# Boat.net
KiCad netlist of a schematic drawn in EAGLE
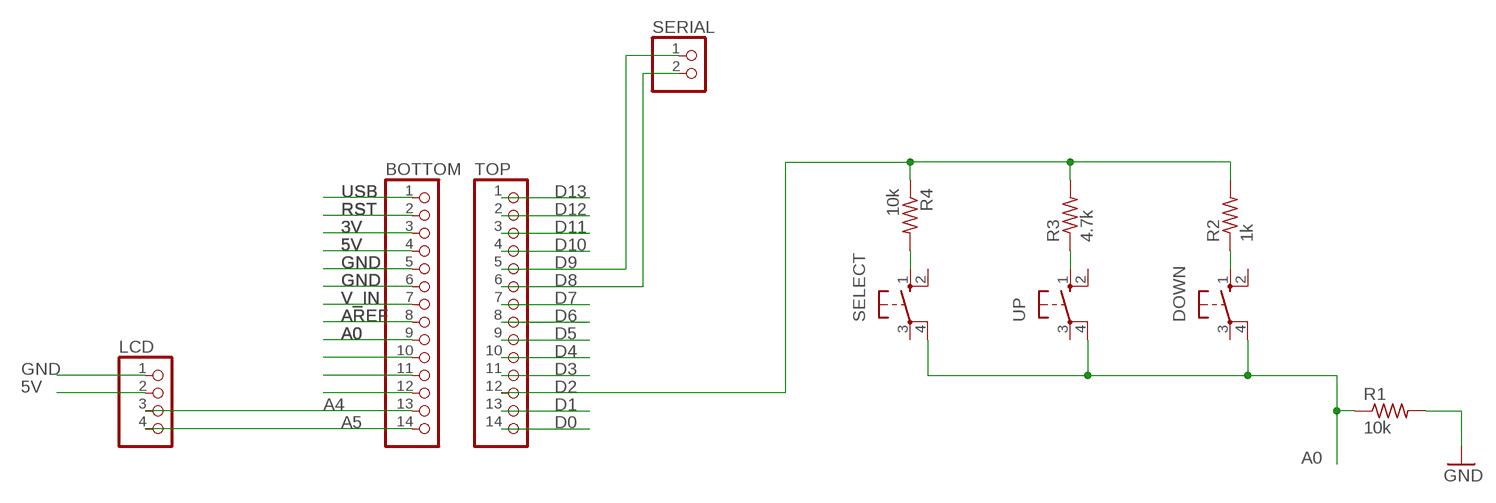
[diagram p0: schematic, sheet 1]

(export (version "E")
  (design (tool "Eeschema 10.0.6"))
  (components
    (comp (ref "BOTTOM")
      (value "PINHD-1X14")
      (footprint "eagle-import:1X14")
      (libsource (lib "eagle-import") (part "PINHD-1X14"))
    )
    (comp (ref "DOWN")
      (value "10-XX")
      (footprint "eagle-import:B3F-10XX")
      (fields (field (name "MPN") "B3F-1000"))
      (libsource (lib "eagle-import") (part "10-XX"))
    )
    (comp (ref "LCD")
      (value "PINHD-1X4")
      (footprint "eagle-import:1X04")
      (libsource (lib "eagle-import") (part "PINHD-1X4"))
    )
    (comp (ref "R1")
      (value "10k")
      (footprint "eagle-import:0204_7")
      (libsource (lib "eagle-import") (part "R-US_0204/7"))
    )
    (comp (ref "R2")
      (value "1k")
      (footprint "eagle-import:0204_7")
      (libsource (lib "eagle-import") (part "R-US_0204/7"))
    )
    (comp (ref "R3")
      (value "4.7k")
      (footprint "eagle-import:0204_7")
      (libsource (lib "eagle-import") (part "R-US_0204/7"))
    )
    (comp (ref "R4")
      (value "10k")
      (footprint "eagle-import:0204_7")
      (libsource (lib "eagle-import") (part "R-US_0204/7"))
    )
    (comp (ref "SELECT")
      (value "10-XX")
      (footprint "eagle-import:B3F-10XX")
      (fields (field (name "MPN") "B3F-1000"))
      (libsource (lib "eagle-import") (part "10-XX"))
    )
    (comp (ref "SERIAL")
      (value "PINHD-1X2")
      (footprint "eagle-import:1X02")
      (libsource (lib "eagle-import") (part "PINHD-1X2"))
    )
    (comp (ref "TOP")
      (value "PINHD-1X14")
      (footprint "eagle-import:1X14")
      (libsource (lib "eagle-import") (part "PINHD-1X14"))
    )
    (comp (ref "UP")
      (value "10-XX")
      (footprint "eagle-import:B3F-10XX")
      (fields (field (name "MPN") "B3F-1000"))
      (libsource (lib "eagle-import") (part "10-XX"))
    )
  )
  (nets
    (net (code "1") (name "/3V") (class "Default")
      (node (ref "BOTTOM") (pin "3") (pinfunction "3_3") (pintype "passive"))
    )
    (net (code "2") (name "/5V") (class "Default")
      (node (ref "BOTTOM") (pin "4") (pinfunction "4_4") (pintype "passive"))
      (node (ref "LCD") (pin "2") (pinfunction "2_2") (pintype "passive"))
    )
    (net (code "3") (name "/A0") (class "Default")
      (node (ref "BOTTOM") (pin "9") (pinfunction "9_9") (pintype "passive"))
      (node (ref "DOWN") (pin "4") (pinfunction "P1_4") (pintype "passive"))
      (node (ref "R1") (pin "1") (pinfunction "1_1") (pintype "passive"))
      (node (ref "SELECT") (pin "4") (pinfunction "P1_4") (pintype "passive"))
      (node (ref "UP") (pin "4") (pinfunction "P1_4") (pintype "passive"))
    )
    (net (code "4") (name "/A4") (class "Default")
      (node (ref "BOTTOM") (pin "13") (pinfunction "13_13") (pintype "passive"))
      (node (ref "LCD") (pin "3") (pinfunction "3_3") (pintype "passive"))
    )
    (net (code "5") (name "/A5") (class "Default")
      (node (ref "BOTTOM") (pin "14") (pinfunction "14_14") (pintype "passive"))
      (node (ref "LCD") (pin "4") (pinfunction "4_4") (pintype "passive"))
    )
    (net (code "6") (name "/AREF") (class "Default")
      (node (ref "BOTTOM") (pin "8") (pinfunction "8_8") (pintype "passive"))
    )
    (net (code "7") (name "/D0") (class "Default")
      (node (ref "TOP") (pin "14") (pinfunction "14_14") (pintype "passive"))
    )
    (net (code "8") (name "/D1") (class "Default")
      (node (ref "TOP") (pin "13") (pinfunction "13_13") (pintype "passive"))
    )
    (net (code "9") (name "/D2") (class "Default")
      (node (ref "R2") (pin "2") (pinfunction "2_2") (pintype "passive"))
      (node (ref "R3") (pin "2") (pinfunction "2_2") (pintype "passive"))
      (node (ref "R4") (pin "1") (pinfunction "1_1") (pintype "passive"))
      (node (ref "TOP") (pin "12") (pinfunction "12_12") (pintype "passive"))
    )
    (net (code "10") (name "/D3") (class "Default")
      (node (ref "TOP") (pin "11") (pinfunction "11_11") (pintype "passive"))
    )
    (net (code "11") (name "/D4") (class "Default")
      (node (ref "TOP") (pin "10") (pinfunction "10_10") (pintype "passive"))
    )
    (net (code "12") (name "/D5") (class "Default")
      (node (ref "TOP") (pin "9") (pinfunction "9_9") (pintype "passive"))
    )
    (net (code "13") (name "/D6") (class "Default")
      (node (ref "TOP") (pin "8") (pinfunction "8_8") (pintype "passive"))
    )
    (net (code "14") (name "/D7") (class "Default")
      (node (ref "TOP") (pin "7") (pinfunction "7_7") (pintype "passive"))
    )
    (net (code "15") (name "/D8") (class "Default")
      (node (ref "SERIAL") (pin "2") (pinfunction "2_2") (pintype "passive"))
      (node (ref "TOP") (pin "6") (pinfunction "6_6") (pintype "passive"))
    )
    (net (code "16") (name "/D9") (class "Default")
      (node (ref "SERIAL") (pin "1") (pinfunction "1_1") (pintype "passive"))
      (node (ref "TOP") (pin "5") (pinfunction "5_5") (pintype "passive"))
    )
    (net (code "17") (name "/D10") (class "Default")
      (node (ref "TOP") (pin "4") (pinfunction "4_4") (pintype "passive"))
    )
    (net (code "18") (name "/D11") (class "Default")
      (node (ref "TOP") (pin "3") (pinfunction "3_3") (pintype "passive"))
    )
    (net (code "19") (name "/D12") (class "Default")
      (node (ref "TOP") (pin "2") (pinfunction "2_2") (pintype "passive"))
    )
    (net (code "20") (name "/D13") (class "Default")
      (node (ref "TOP") (pin "1") (pinfunction "1_1") (pintype "passive"))
    )
    (net (code "21") (name "/RST") (class "Default")
      (node (ref "BOTTOM") (pin "2") (pinfunction "2_2") (pintype "passive"))
    )
    (net (code "22") (name "/USB") (class "Default")
      (node (ref "BOTTOM") (pin "1") (pinfunction "1_1") (pintype "passive"))
    )
    (net (code "23") (name "/V_IN") (class "Default")
      (node (ref "BOTTOM") (pin "7") (pinfunction "7_7") (pintype "passive"))
    )
    (net (code "24") (name "GND") (class "Default")
      (node (ref "BOTTOM") (pin "5") (pinfunction "5_5") (pintype "passive"))
      (node (ref "BOTTOM") (pin "6") (pinfunction "6_6") (pintype "passive"))
      (node (ref "LCD") (pin "1") (pinfunction "1_1") (pintype "passive"))
      (node (ref "R1") (pin "2") (pinfunction "2_2") (pintype "passive"))
    )
    (net (code "25") (name "Net-(DOWN-S)") (class "Default")
      (node (ref "DOWN") (pin "1") (pinfunction "S_1") (pintype "passive"))
      (node (ref "R2") (pin "1") (pinfunction "1_1") (pintype "passive"))
    )
    (net (code "26") (name "Net-(SELECT-S)") (class "Default")
      (node (ref "R4") (pin "2") (pinfunction "2_2") (pintype "passive"))
      (node (ref "SELECT") (pin "1") (pinfunction "S_1") (pintype "passive"))
    )
    (net (code "27") (name "Net-(UP-S)") (class "Default")
      (node (ref "R3") (pin "1") (pinfunction "1_1") (pintype "passive"))
      (node (ref "UP") (pin "1") (pinfunction "S_1") (pintype "passive"))
    )
    (net (code "28") (name "unconnected-(BOTTOM-Pad10)") (class "Default")
      (node (ref "BOTTOM") (pin "10") (pinfunction "10_10") (pintype "passive"))
    )
    (net (code "29") (name "unconnected-(BOTTOM-Pad11)") (class "Default")
      (node (ref "BOTTOM") (pin "11") (pinfunction "11_11") (pintype "passive"))
    )
    (net (code "30") (name "unconnected-(BOTTOM-Pad12)") (class "Default")
      (node (ref "BOTTOM") (pin "12") (pinfunction "12_12") (pintype "passive"))
    )
    (net (code "31") (name "unconnected-(DOWN-P-Pad3)") (class "Default")
      (node (ref "DOWN") (pin "3") (pinfunction "P_3") (pintype "passive"))
    )
    (net (code "32") (name "unconnected-(DOWN-S1-Pad2)") (class "Default")
      (node (ref "DOWN") (pin "2") (pinfunction "S1_2") (pintype "passive"))
    )
    (net (code "33") (name "unconnected-(SELECT-P-Pad3)") (class "Default")
      (node (ref "SELECT") (pin "3") (pinfunction "P_3") (pintype "passive"))
    )
    (net (code "34") (name "unconnected-(SELECT-S1-Pad2)") (class "Default")
      (node (ref "SELECT") (pin "2") (pinfunction "S1_2") (pintype "passive"))
    )
    (net (code "35") (name "unconnected-(UP-P-Pad3)") (class "Default")
      (node (ref "UP") (pin "3") (pinfunction "P_3") (pintype "passive"))
    )
    (net (code "36") (name "unconnected-(UP-S1-Pad2)") (class "Default")
      (node (ref "UP") (pin "2") (pinfunction "S1_2") (pintype "passive"))
    )
  )
)
